# msr501.net
KiCad netlist of a schematic drawn in Altium Designer
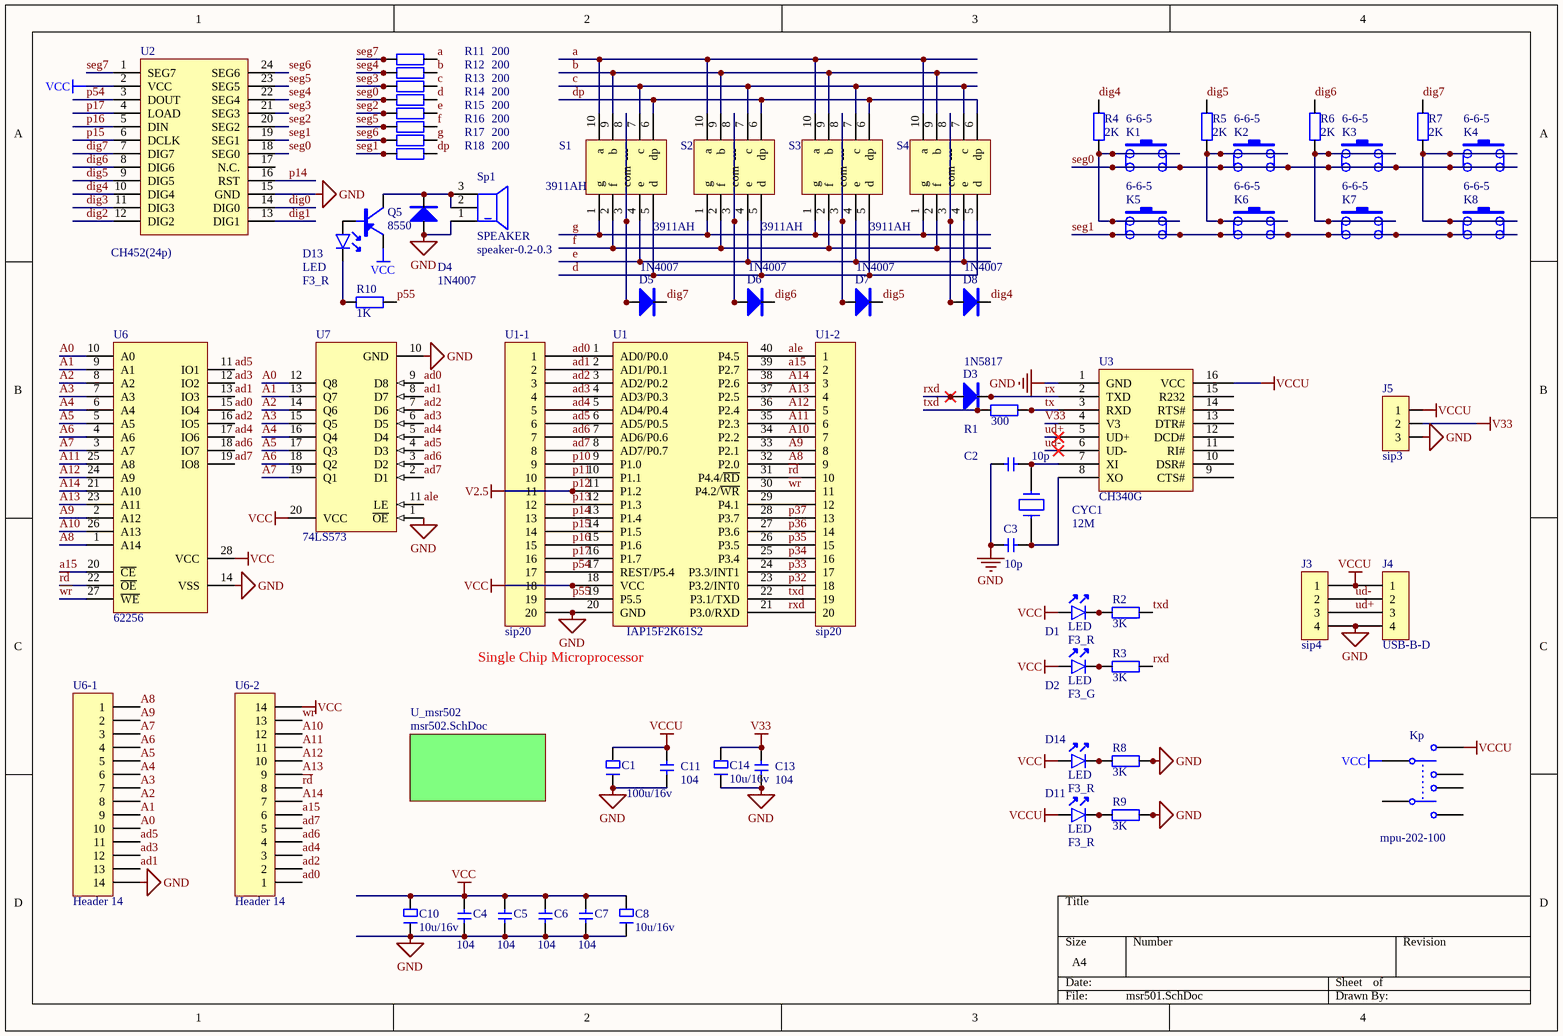
[diagram p0: msr501.SchDoc]

(export (version "E")
  (design (tool "Eeschema 10.0.6"))
  (components
    (comp (ref "C1")
      (value "100u/16v")
      (footprint "rb.1/.2")
      (description "Electrolytic Capacitor")
      (libsource (lib "msr3") (part "ELECTRO1"))
    )
    (comp (ref "C2")
      (value "10p")
      (footprint "CAP010805")
      (fields (field (name "Comment") "CAP"))
      (libsource (lib "lab_iap") (part "CAP"))
    )
    (comp (ref "C3")
      (value "10p")
      (footprint "CAP010805")
      (fields (field (name "Comment") "CAP"))
      (libsource (lib "lab_iap") (part "CAP"))
    )
    (comp (ref "C4")
      (value "104")
      (footprint "CAP010805")
      (description "Capacitor")
      (libsource (lib "*") (part "CAP"))
    )
    (comp (ref "C5")
      (value "104")
      (footprint "CAP010805")
      (description "Capacitor")
      (libsource (lib "*") (part "CAP"))
    )
    (comp (ref "C6")
      (value "104")
      (footprint "CAP010805")
      (description "Capacitor")
      (libsource (lib "m2t1") (part "CAP"))
    )
    (comp (ref "C7")
      (value "104")
      (footprint "CAP010805")
      (description "Capacitor")
      (libsource (lib "*") (part "CAP"))
    )
    (comp (ref "C8")
      (value "10u/16v")
      (footprint "rb.1/.2")
      (description "Electrolytic Capacitor")
      (fields (field (name "Comment") "100u/16v"))
      (libsource (lib "msr3") (part "ELECTRO1"))
    )
    (comp (ref "C10")
      (value "10u/16v")
      (footprint "rb.1/.2")
      (description "Electrolytic Capacitor")
      (fields (field (name "Comment") "100u/16v"))
      (libsource (lib "msr3") (part "ELECTRO1"))
    )
    (comp (ref "C11")
      (value "104")
      (footprint "CAP010805")
      (description "Capacitor")
      (libsource (lib "*") (part "CAP"))
    )
    (comp (ref "C13")
      (value "104")
      (footprint "CAP010805")
      (description "Capacitor")
      (fields (field (name "ALTIUM_VALUE") "104"))
      (libsource (lib "*") (part "CAP"))
    )
    (comp (ref "C14")
      (value "10u/16v")
      (footprint "rb.1/.2")
      (description "Electrolytic Capacitor")
      (libsource (lib "msr3") (part "ELECTRO1"))
    )
    (comp (ref "CYC1")
      (value "12M")
      (footprint "cyc-rad")
      (description "Crystal")
      (fields (field (name "Comment") "12Mhz"))
      (libsource (lib "*") (part "CRYSTAL"))
    )
    (comp (ref "D1")
      (value "LED")
      (footprint "led-3")
      (fields (field (name "ALTIUM_VALUE") "F3_R"))
      (libsource (lib "PCB_prj3") (part "LED"))
    )
    (comp (ref "D2")
      (value "LED")
      (footprint "led-3")
      (fields (field (name "ALTIUM_VALUE") "F3_G"))
      (libsource (lib "PCB_prj3") (part "LED"))
    )
    (comp (ref "D3")
      (value "1N5817")
      (footprint "smc03")
      (fields (field (name "Comment") "sma03"))
      (libsource (lib "mpll3") (part "sma03"))
    )
    (comp (ref "D4")
      (value "1N4007")
      (footprint "smc03")
      (fields (field (name "Comment") "sma03"))
      (libsource (lib "mpll3") (part "sma03"))
    )
    (comp (ref "D5")
      (value "1N4007")
      (footprint "smc03")
      (fields (field (name "Comment") "sma03"))
      (libsource (lib "mpll3") (part "sma03"))
    )
    (comp (ref "D6")
      (value "1N4007")
      (footprint "smc03")
      (fields (field (name "Comment") "sma03"))
      (libsource (lib "mpll3") (part "sma03"))
    )
    (comp (ref "D7")
      (value "1N4007")
      (footprint "smc03")
      (fields (field (name "Comment") "sma03"))
      (libsource (lib "mpll3") (part "sma03"))
    )
    (comp (ref "D8")
      (value "1N4007")
      (footprint "smc03")
      (fields (field (name "Comment") "sma03"))
      (libsource (lib "mpll3") (part "sma03"))
    )
    (comp (ref "D11")
      (value "LED")
      (footprint "led-3")
      (fields (field (name "ALTIUM_VALUE") "F3_R"))
      (libsource (lib "PCB_prj3") (part "LED"))
    )
    (comp (ref "D13")
      (value "LED")
      (footprint "led-3")
      (fields (field (name "ALTIUM_VALUE") "F3_R"))
      (libsource (lib "") (part "LED_1"))
    )
    (comp (ref "D14")
      (value "LED")
      (footprint "led-3")
      (fields (field (name "ALTIUM_VALUE") "F3_R"))
      (libsource (lib "PCB_prj3") (part "LED"))
    )
    (comp (ref "J3")
      (value "sip4")
      (footprint "SIP4")
      (description "Connector")
      (fields (field (name "Comment") "USB-a"))
      (libsource (lib "") (part "CON4_1"))
    )
    (comp (ref "J4")
      (value "USB-B-D")
      (footprint "USB_b")
      (description "Connector")
      (libsource (lib "MyInt_Lib") (part "CON4"))
    )
    (comp (ref "J5")
      (value "sip3")
      (footprint "SIP3")
      (description "Connector")
      (fields (field (name "Comment") "CON3"))
      (libsource (lib "mtr1_1") (part "CON3"))
    )
    (comp (ref "K1") (value "6-6-5") (footprint "pb6_6") (libsource (lib "*") (part "SW-PB2")))
    (comp (ref "K2") (value "6-6-5") (footprint "pb6_6") (libsource (lib "*") (part "SW-PB2")))
    (comp (ref "K3") (value "6-6-5") (footprint "pb6_6") (libsource (lib "*") (part "SW-PB2")))
    (comp (ref "K4") (value "6-6-5") (footprint "pb6_6") (libsource (lib "*") (part "SW-PB2")))
    (comp (ref "K5") (value "6-6-5") (footprint "pb6_6") (libsource (lib "*") (part "SW-PB2")))
    (comp (ref "K6") (value "6-6-5") (footprint "pb6_6") (libsource (lib "*") (part "SW-PB2")))
    (comp (ref "K7") (value "6-6-5") (footprint "pb6_6") (libsource (lib "*") (part "SW-PB2")))
    (comp (ref "K8") (value "6-6-5") (footprint "pb6_6") (libsource (lib "*") (part "SW-PB2")))
    (comp (ref "Kp")
      (value "mpu-202-100")
      (footprint "DPDT-6")
      (description "Double-Pole, Double-Throw Switch")
      (fields (field (name "Comment") "SW-DPDT") (field (name "PUBLISHER") "Altium Limited"))
      (libsource (lib "m2t3") (part "SW-DPDT"))
    )
    (comp (ref "Q5") (value "8550") (footprint "to-92a") (libsource (lib "PCB_prj3") (part "PNP")))
    (comp (ref "R1")
      (value "300")
      (footprint "a038050")
      (description "Resistor")
      (fields (field (name "Comment") "Res2") (field (name "PUBLISHER") "Altium Limited"))
      (libsource (lib "msr4") (part "Res22"))
    )
    (comp (ref "R2")
      (value "3K")
      (footprint "a038050")
      (description "Resistor")
      (fields (field (name "Comment") "Res2") (field (name "PUBLISHER") "Altium Limited"))
      (libsource (lib "msr4") (part "Res22"))
    )
    (comp (ref "R3")
      (value "3K")
      (footprint "a038050")
      (description "Resistor")
      (fields (field (name "Comment") "Res2") (field (name "PUBLISHER") "Altium Limited"))
      (libsource (lib "msr4") (part "Res22"))
    )
    (comp (ref "R4")
      (value "2K")
      (footprint "a038050")
      (description "Resistor")
      (fields (field (name "Comment") "Res2") (field (name "PUBLISHER") "Altium Limited"))
      (libsource (lib "") (part "Res22_1"))
    )
    (comp (ref "R5")
      (value "2K")
      (footprint "a038050")
      (description "Resistor")
      (fields (field (name "Comment") "Res2") (field (name "PUBLISHER") "Altium Limited"))
      (libsource (lib "") (part "Res22_1"))
    )
    (comp (ref "R6")
      (value "2K")
      (footprint "a038050")
      (description "Resistor")
      (fields (field (name "Comment") "Res2") (field (name "PUBLISHER") "Altium Limited"))
      (libsource (lib "") (part "Res22_1"))
    )
    (comp (ref "R7")
      (value "2K")
      (footprint "a038050")
      (description "Resistor")
      (fields (field (name "Comment") "Res2") (field (name "PUBLISHER") "Altium Limited"))
      (libsource (lib "") (part "Res22_1"))
    )
    (comp (ref "R8")
      (value "3K")
      (footprint "a038050")
      (description "Resistor")
      (fields (field (name "Comment") "Res2") (field (name "PUBLISHER") "Altium Limited"))
      (libsource (lib "msr4") (part "Res22"))
    )
    (comp (ref "R9")
      (value "3K")
      (footprint "a038050")
      (description "Resistor")
      (fields (field (name "Comment") "Res2") (field (name "PUBLISHER") "Altium Limited"))
      (libsource (lib "msr4") (part "Res22"))
    )
    (comp (ref "R10")
      (value "1K")
      (footprint "a038050")
      (description "Resistor")
      (fields (field (name "Comment") "Res2") (field (name "PUBLISHER") "Altium Limited"))
      (libsource (lib "msr4") (part "Res22"))
    )
    (comp (ref "R11")
      (value "200")
      (footprint "a038050")
      (description "Resistor")
      (fields (field (name "Comment") "Res2") (field (name "PUBLISHER") "Altium Limited"))
      (libsource (lib "msr4") (part "Res22"))
    )
    (comp (ref "R12")
      (value "200")
      (footprint "a038050")
      (description "Resistor")
      (fields (field (name "Comment") "Res2") (field (name "PUBLISHER") "Altium Limited"))
      (libsource (lib "msr4") (part "Res22"))
    )
    (comp (ref "R13")
      (value "200")
      (footprint "a038050")
      (description "Resistor")
      (fields (field (name "Comment") "Res2") (field (name "PUBLISHER") "Altium Limited"))
      (libsource (lib "msr4") (part "Res22"))
    )
    (comp (ref "R14")
      (value "200")
      (footprint "a038050")
      (description "Resistor")
      (fields (field (name "Comment") "Res2") (field (name "PUBLISHER") "Altium Limited"))
      (libsource (lib "msr4") (part "Res22"))
    )
    (comp (ref "R15")
      (value "200")
      (footprint "a038050")
      (description "Resistor")
      (fields (field (name "Comment") "Res2") (field (name "PUBLISHER") "Altium Limited"))
      (libsource (lib "msr4") (part "Res22"))
    )
    (comp (ref "R16")
      (value "200")
      (footprint "a038050")
      (description "Resistor")
      (fields (field (name "Comment") "Res2") (field (name "PUBLISHER") "Altium Limited"))
      (libsource (lib "msr4") (part "Res22"))
    )
    (comp (ref "R17")
      (value "200")
      (footprint "a038050")
      (description "Resistor")
      (fields (field (name "Comment") "Res2") (field (name "PUBLISHER") "Altium Limited"))
      (libsource (lib "msr4") (part "Res22"))
    )
    (comp (ref "R18")
      (value "200")
      (footprint "a038050")
      (description "Resistor")
      (fields (field (name "Comment") "Res2") (field (name "PUBLISHER") "Altium Limited"))
      (libsource (lib "msr4") (part "Res22"))
    )
    (comp (ref "S1") (value "3911AH") (footprint "LED10s") (libsource (lib "m2t1") (part "DS1")))
    (comp (ref "S2") (value "3911AH") (footprint "LED10s") (libsource (lib "m2t1") (part "DS1")))
    (comp (ref "S3") (value "3911AH") (footprint "LED10s") (libsource (lib "m2t1") (part "DS1")))
    (comp (ref "S4") (value "3911AH") (footprint "LED10s") (libsource (lib "m2t1") (part "DS1")))
    (comp (ref "Sp1")
      (value "SPEAKER")
      (footprint "sp0.23")
      (description "SPEAKER sip0.2/0.3")
      (fields (field (name "ALTIUM_VALUE") "speaker-0.2-0.3"))
      (libsource (lib "m2t5") (part "SPEAKER"))
    )
    (comp (ref "U1")
      (value "IAP15F2K61S2")
      (footprint "DIP40")
      (fields (field (name "Comment") "单片机IAP15F2K61S2"))
      (libsource (lib "NEW") (part "Component_3"))
    )
    (comp (ref "U1-1")
      (value "sip20")
      (footprint "msr2:HDR1X20")
      (description "Header, 20-Pin")
      (fields (field (name "Comment") "Header 20") (field (name "PUBLISHER") "Altium Limited"))
      (libsource (lib "Miscellaneous Connectors") (part "Header 20"))
    )
    (comp (ref "U1-2")
      (value "sip20")
      (footprint "HDR1X20")
      (description "Header, 20-Pin")
      (fields (field (name "Comment") "Header 20") (field (name "PUBLISHER") "Altium Limited"))
      (libsource (lib "") (part "Header 20_1"))
    )
    (comp (ref "U2")
      (value "CH452(24p)")
      (footprint "dip24")
      (fields (field (name "Comment") "CH451"))
      (libsource (lib "*") (part "CH451"))
    )
    (comp (ref "U3") (value "CH340G") (footprint "SOP-16") (libsource (lib "msr") (part "CH340G")))
    (comp (ref "U6") (value "62256") (footprint "62256") (libsource (lib "MyLib") (part "62256")))
    (comp (ref "U6-1")
      (value "Header 14")
      (footprint "HDR1X14C")
      (description "Header, 14-Pin")
      (fields (field (name "PUBLISHER") "Altium Limited"))
      (libsource (lib "Miscellaneous Connectors") (part "Header 14"))
    )
    (comp (ref "U6-2")
      (value "Header 14")
      (footprint "HDR1X14C")
      (description "Header, 14-Pin")
      (fields (field (name "PUBLISHER") "Altium Limited"))
      (libsource (lib "") (part "Header 14_1"))
    )
    (comp (ref "U7")
      (value "74LS573")
      (footprint "DIP20")
      (description "Octal D Latch with 3-State Output")
      (fields (field (name "Comment") "DM74LS573N") (field (name "PUBLISHER") "Altium Limited"))
      (libsource (lib "FSC Logic Latch") (part "DM74LS573N"))
    )
  )
  (nets
    (net (code "2") (name "/A0") (class "Default")
      (node (ref "U6") (pin "10") (pinfunction "A0_10") (pintype "passive"))
      (node (ref "U6-1") (pin "10") (pinfunction "10_10") (pintype "passive"))
      (node (ref "U7") (pin "12") (pinfunction "Q8_12") (pintype "tri_state"))
    )
    (net (code "3") (name "/A1") (class "Default")
      (node (ref "U6") (pin "9") (pinfunction "A1_9") (pintype "passive"))
      (node (ref "U6-1") (pin "9") (pinfunction "9_9") (pintype "passive"))
      (node (ref "U7") (pin "13") (pinfunction "Q7_13") (pintype "tri_state"))
    )
    (net (code "4") (name "/A2") (class "Default")
      (node (ref "U6") (pin "8") (pinfunction "A2_8") (pintype "passive"))
      (node (ref "U6-1") (pin "8") (pinfunction "8_8") (pintype "passive"))
      (node (ref "U7") (pin "14") (pinfunction "Q6_14") (pintype "tri_state"))
    )
    (net (code "5") (name "/A3") (class "Default")
      (node (ref "U6") (pin "7") (pinfunction "A3_7") (pintype "passive"))
      (node (ref "U6-1") (pin "7") (pinfunction "7_7") (pintype "passive"))
      (node (ref "U7") (pin "15") (pinfunction "Q5_15") (pintype "tri_state"))
    )
    (net (code "6") (name "/A4") (class "Default")
      (node (ref "U6") (pin "6") (pinfunction "A4_6") (pintype "passive"))
      (node (ref "U6-1") (pin "6") (pinfunction "6_6") (pintype "passive"))
      (node (ref "U7") (pin "16") (pinfunction "Q4_16") (pintype "tri_state"))
    )
    (net (code "7") (name "/A5") (class "Default")
      (node (ref "U6") (pin "5") (pinfunction "A5_5") (pintype "passive"))
      (node (ref "U6-1") (pin "5") (pinfunction "5_5") (pintype "passive"))
      (node (ref "U7") (pin "17") (pinfunction "Q3_17") (pintype "tri_state"))
    )
    (net (code "8") (name "/A6") (class "Default")
      (node (ref "U6") (pin "4") (pinfunction "A6_4") (pintype "passive"))
      (node (ref "U6-1") (pin "4") (pinfunction "4_4") (pintype "passive"))
      (node (ref "U7") (pin "18") (pinfunction "Q2_18") (pintype "tri_state"))
    )
    (net (code "9") (name "/A7") (class "Default")
      (node (ref "U6") (pin "3") (pinfunction "A7_3") (pintype "passive"))
      (node (ref "U6-1") (pin "3") (pinfunction "3_3") (pintype "passive"))
      (node (ref "U7") (pin "19") (pinfunction "Q1_19") (pintype "tri_state"))
    )
    (net (code "10") (name "/A8") (class "Default")
      (node (ref "U1") (pin "32") (pinfunction "P2.0_32") (pintype "passive"))
      (node (ref "U1-2") (pin "9") (pinfunction "9_9") (pintype "passive"))
      (node (ref "U6") (pin "1") (pinfunction "A14_1") (pintype "passive"))
      (node (ref "U6-1") (pin "1") (pinfunction "1_1") (pintype "passive"))
    )
    (net (code "11") (name "/A9") (class "Default")
      (node (ref "U1") (pin "33") (pinfunction "P2.1_33") (pintype "passive"))
      (node (ref "U1-2") (pin "8") (pinfunction "8_8") (pintype "passive"))
      (node (ref "U6") (pin "2") (pinfunction "A12_2") (pintype "passive"))
      (node (ref "U6-1") (pin "2") (pinfunction "2_2") (pintype "passive"))
    )
    (net (code "12") (name "/A10") (class "Default")
      (node (ref "U1") (pin "34") (pinfunction "P2.2_34") (pintype "passive"))
      (node (ref "U1-2") (pin "7") (pinfunction "7_7") (pintype "passive"))
      (node (ref "U6") (pin "26") (pinfunction "A13_26") (pintype "passive"))
      (node (ref "U6-2") (pin "12") (pinfunction "12_12") (pintype "passive"))
    )
    (net (code "13") (name "/A11") (class "Default")
      (node (ref "U1") (pin "35") (pinfunction "P2.3_35") (pintype "passive"))
      (node (ref "U1-2") (pin "6") (pinfunction "6_6") (pintype "passive"))
      (node (ref "U6") (pin "25") (pinfunction "A8_25") (pintype "passive"))
      (node (ref "U6-2") (pin "11") (pinfunction "11_11") (pintype "passive"))
    )
    (net (code "14") (name "/A12") (class "Default")
      (node (ref "U1") (pin "36") (pinfunction "P2.4_36") (pintype "passive"))
      (node (ref "U1-2") (pin "5") (pinfunction "5_5") (pintype "passive"))
      (node (ref "U6") (pin "24") (pinfunction "A9_24") (pintype "passive"))
      (node (ref "U6-2") (pin "10") (pinfunction "10_10") (pintype "passive"))
    )
    (net (code "15") (name "/A13") (class "Default")
      (node (ref "U1") (pin "37") (pinfunction "P2.5_37") (pintype "passive"))
      (node (ref "U1-2") (pin "4") (pinfunction "4_4") (pintype "passive"))
      (node (ref "U6") (pin "23") (pinfunction "A11_23") (pintype "passive"))
      (node (ref "U6-2") (pin "9") (pinfunction "9_9") (pintype "passive"))
    )
    (net (code "16") (name "/A14") (class "Default")
      (node (ref "U1") (pin "38") (pinfunction "P2.6_38") (pintype "passive"))
      (node (ref "U1-2") (pin "3") (pinfunction "3_3") (pintype "passive"))
      (node (ref "U6") (pin "21") (pinfunction "A10_21") (pintype "passive"))
      (node (ref "U6-2") (pin "7") (pinfunction "7_7") (pintype "passive"))
    )
    (net (code "17") (name "/a") (class "Default")
      (node (ref "R11") (pin "1") (pinfunction "1_1") (pintype "passive"))
      (node (ref "R11") (pin "3") (pinfunction "3_3") (pintype "passive"))
      (node (ref "S1") (pin "10") (pinfunction "a_10") (pintype "passive"))
      (node (ref "S2") (pin "10") (pinfunction "a_10") (pintype "passive"))
      (node (ref "S3") (pin "10") (pinfunction "a_10") (pintype "passive"))
      (node (ref "S4") (pin "10") (pinfunction "a_10") (pintype "passive"))
    )
    (net (code "18") (name "/a15") (class "Default")
      (node (ref "U1") (pin "39") (pinfunction "P2.7_39") (pintype "passive"))
      (node (ref "U1-2") (pin "2") (pinfunction "2_2") (pintype "passive"))
      (node (ref "U6") (pin "20") (pinfunction "~{CE}_20") (pintype "passive"))
      (node (ref "U6-2") (pin "6") (pinfunction "6_6") (pintype "passive"))
    )
    (net (code "19") (name "/ad0") (class "Default")
      (node (ref "U1") (pin "1") (pinfunction "AD0/P0.0_1") (pintype "passive"))
      (node (ref "U1-1") (pin "1") (pinfunction "1_1") (pintype "passive"))
      (node (ref "U6") (pin "15") (pinfunction "IO4_15") (pintype "passive"))
      (node (ref "U6-2") (pin "1") (pinfunction "1_1") (pintype "passive"))
      (node (ref "U7") (pin "9") (pinfunction "D8_9") (pintype "input"))
    )
    (net (code "20") (name "/ad1") (class "Default")
      (node (ref "U1") (pin "2") (pinfunction "AD1/P0.1_2") (pintype "passive"))
      (node (ref "U1-1") (pin "2") (pinfunction "2_2") (pintype "passive"))
      (node (ref "U6") (pin "13") (pinfunction "IO3_13") (pintype "passive"))
      (node (ref "U6-1") (pin "13") (pinfunction "13_13") (pintype "passive"))
      (node (ref "U7") (pin "8") (pinfunction "D7_8") (pintype "input"))
    )
    (net (code "21") (name "/ad2") (class "Default")
      (node (ref "U1") (pin "3") (pinfunction "AD2/P0.2_3") (pintype "passive"))
      (node (ref "U1-1") (pin "3") (pinfunction "3_3") (pintype "passive"))
      (node (ref "U6") (pin "16") (pinfunction "IO5_16") (pintype "passive"))
      (node (ref "U6-2") (pin "2") (pinfunction "2_2") (pintype "passive"))
      (node (ref "U7") (pin "7") (pinfunction "D6_7") (pintype "input"))
    )
    (net (code "22") (name "/ad3") (class "Default")
      (node (ref "U1") (pin "4") (pinfunction "AD3/P0.3_4") (pintype "passive"))
      (node (ref "U1-1") (pin "4") (pinfunction "4_4") (pintype "passive"))
      (node (ref "U6") (pin "12") (pinfunction "IO2_12") (pintype "passive"))
      (node (ref "U6-1") (pin "12") (pinfunction "12_12") (pintype "passive"))
      (node (ref "U7") (pin "6") (pinfunction "D5_6") (pintype "input"))
    )
    (net (code "23") (name "/ad4") (class "Default")
      (node (ref "U1") (pin "5") (pinfunction "AD4/P0.4_5") (pintype "passive"))
      (node (ref "U1-1") (pin "5") (pinfunction "5_5") (pintype "passive"))
      (node (ref "U6") (pin "17") (pinfunction "IO6_17") (pintype "passive"))
      (node (ref "U6-2") (pin "3") (pinfunction "3_3") (pintype "passive"))
      (node (ref "U7") (pin "5") (pinfunction "D4_5") (pintype "input"))
    )
    (net (code "24") (name "/ad5") (class "Default")
      (node (ref "U1") (pin "6") (pinfunction "AD5/P0.5_6") (pintype "passive"))
      (node (ref "U1-1") (pin "6") (pinfunction "6_6") (pintype "passive"))
      (node (ref "U6") (pin "11") (pinfunction "IO1_11") (pintype "passive"))
      (node (ref "U6-1") (pin "11") (pinfunction "11_11") (pintype "passive"))
      (node (ref "U7") (pin "4") (pinfunction "D3_4") (pintype "input"))
    )
    (net (code "25") (name "/ad6") (class "Default")
      (node (ref "U1") (pin "7") (pinfunction "AD6/P0.6_7") (pintype "passive"))
      (node (ref "U1-1") (pin "7") (pinfunction "7_7") (pintype "passive"))
      (node (ref "U6") (pin "18") (pinfunction "IO7_18") (pintype "passive"))
      (node (ref "U6-2") (pin "4") (pinfunction "4_4") (pintype "passive"))
      (node (ref "U7") (pin "3") (pinfunction "D2_3") (pintype "input"))
    )
    (net (code "26") (name "/ad7") (class "Default")
      (node (ref "U1") (pin "8") (pinfunction "AD7/P0.7_8") (pintype "passive"))
      (node (ref "U1-1") (pin "8") (pinfunction "8_8") (pintype "passive"))
      (node (ref "U6") (pin "19") (pinfunction "IO8_19") (pintype "passive"))
      (node (ref "U6-2") (pin "5") (pinfunction "5_5") (pintype "passive"))
      (node (ref "U7") (pin "2") (pinfunction "D1_2") (pintype "input"))
    )
    (net (code "27") (name "/ale") (class "Default")
      (node (ref "U1") (pin "40") (pinfunction "P4.5_40") (pintype "passive"))
      (node (ref "U1-2") (pin "1") (pinfunction "1_1") (pintype "passive"))
      (node (ref "U7") (pin "11") (pinfunction "LE_11") (pintype "input"))
    )
    (net (code "28") (name "/b") (class "Default")
      (node (ref "R12") (pin "1") (pinfunction "1_1") (pintype "passive"))
      (node (ref "R12") (pin "3") (pinfunction "3_3") (pintype "passive"))
      (node (ref "S1") (pin "9") (pinfunction "b_9") (pintype "passive"))
      (node (ref "S2") (pin "9") (pinfunction "b_9") (pintype "passive"))
      (node (ref "S3") (pin "9") (pinfunction "b_9") (pintype "passive"))
      (node (ref "S4") (pin "9") (pinfunction "b_9") (pintype "passive"))
    )
    (net (code "29") (name "/c") (class "Default")
      (node (ref "R13") (pin "1") (pinfunction "1_1") (pintype "passive"))
      (node (ref "R13") (pin "3") (pinfunction "3_3") (pintype "passive"))
      (node (ref "S1") (pin "7") (pinfunction "c_7") (pintype "passive"))
      (node (ref "S2") (pin "7") (pinfunction "c_7") (pintype "passive"))
      (node (ref "S3") (pin "7") (pinfunction "c_7") (pintype "passive"))
      (node (ref "S4") (pin "7") (pinfunction "c_7") (pintype "passive"))
    )
    (net (code "30") (name "/d") (class "Default")
      (node (ref "R14") (pin "1") (pinfunction "1_1") (pintype "passive"))
      (node (ref "R14") (pin "3") (pinfunction "3_3") (pintype "passive"))
      (node (ref "S1") (pin "5") (pinfunction "d_5") (pintype "passive"))
      (node (ref "S2") (pin "5") (pinfunction "d_5") (pintype "passive"))
      (node (ref "S3") (pin "5") (pinfunction "d_5") (pintype "passive"))
      (node (ref "S4") (pin "5") (pinfunction "d_5") (pintype "passive"))
    )
    (net (code "31") (name "/dig0") (class "Default")
      (node (ref "U2") (pin "14") (pinfunction "DIG0_14") (pintype "passive"))
    )
    (net (code "32") (name "/dig1") (class "Default")
      (node (ref "U2") (pin "13") (pinfunction "DIG1_13") (pintype "passive"))
    )
    (net (code "33") (name "/dig2") (class "Default")
      (node (ref "U2") (pin "12") (pinfunction "DIG2_12") (pintype "passive"))
    )
    (net (code "34") (name "/dig3") (class "Default")
      (node (ref "U2") (pin "11") (pinfunction "DIG3_11") (pintype "passive"))
    )
    (net (code "35") (name "/dig4") (class "Default")
      (node (ref "D8") (pin "1") (pinfunction "1_1") (pintype "passive"))
      (node (ref "D8") (pin "3") (pinfunction "3_3") (pintype "passive"))
      (node (ref "R4") (pin "2") (pinfunction "2_2") (pintype "passive"))
      (node (ref "R4") (pin "4") (pinfunction "4_4") (pintype "passive"))
      (node (ref "U2") (pin "10") (pinfunction "DIG4_10") (pintype "passive"))
    )
    (net (code "36") (name "/dig5") (class "Default")
      (node (ref "D7") (pin "1") (pinfunction "1_1") (pintype "passive"))
      (node (ref "D7") (pin "3") (pinfunction "3_3") (pintype "passive"))
      (node (ref "R5") (pin "2") (pinfunction "2_2") (pintype "passive"))
      (node (ref "R5") (pin "4") (pinfunction "4_4") (pintype "passive"))
      (node (ref "U2") (pin "9") (pinfunction "DIG5_9") (pintype "passive"))
    )
    (net (code "37") (name "/dig6") (class "Default")
      (node (ref "D6") (pin "1") (pinfunction "1_1") (pintype "passive"))
      (node (ref "D6") (pin "3") (pinfunction "3_3") (pintype "passive"))
      (node (ref "R6") (pin "2") (pinfunction "2_2") (pintype "passive"))
      (node (ref "R6") (pin "4") (pinfunction "4_4") (pintype "passive"))
      (node (ref "U2") (pin "8") (pinfunction "DIG6_8") (pintype "passive"))
    )
    (net (code "38") (name "/dig7") (class "Default")
      (node (ref "D5") (pin "1") (pinfunction "1_1") (pintype "passive"))
      (node (ref "D5") (pin "3") (pinfunction "3_3") (pintype "passive"))
      (node (ref "R7") (pin "2") (pinfunction "2_2") (pintype "passive"))
      (node (ref "R7") (pin "4") (pinfunction "4_4") (pintype "passive"))
      (node (ref "U2") (pin "7") (pinfunction "DIG7_7") (pintype "passive"))
    )
    (net (code "39") (name "/dp") (class "Default")
      (node (ref "R18") (pin "1") (pinfunction "1_1") (pintype "passive"))
      (node (ref "R18") (pin "3") (pinfunction "3_3") (pintype "passive"))
      (node (ref "S1") (pin "6") (pinfunction "dp_6") (pintype "passive"))
      (node (ref "S2") (pin "6") (pinfunction "dp_6") (pintype "passive"))
      (node (ref "S3") (pin "6") (pinfunction "dp_6") (pintype "passive"))
      (node (ref "S4") (pin "6") (pinfunction "dp_6") (pintype "passive"))
    )
    (net (code "40") (name "/e") (class "Default")
      (node (ref "R15") (pin "1") (pinfunction "1_1") (pintype "passive"))
      (node (ref "R15") (pin "3") (pinfunction "3_3") (pintype "passive"))
      (node (ref "S1") (pin "4") (pinfunction "e_4") (pintype "passive"))
      (node (ref "S2") (pin "4") (pinfunction "e_4") (pintype "passive"))
      (node (ref "S3") (pin "4") (pinfunction "e_4") (pintype "passive"))
      (node (ref "S4") (pin "4") (pinfunction "e_4") (pintype "passive"))
    )
    (net (code "41") (name "/f") (class "Default")
      (node (ref "R16") (pin "1") (pinfunction "1_1") (pintype "passive"))
      (node (ref "R16") (pin "3") (pinfunction "3_3") (pintype "passive"))
      (node (ref "S1") (pin "2") (pinfunction "f_2") (pintype "passive"))
      (node (ref "S2") (pin "2") (pinfunction "f_2") (pintype "passive"))
      (node (ref "S3") (pin "2") (pinfunction "f_2") (pintype "passive"))
      (node (ref "S4") (pin "2") (pinfunction "f_2") (pintype "passive"))
    )
    (net (code "42") (name "/g") (class "Default")
      (node (ref "R17") (pin "1") (pinfunction "1_1") (pintype "passive"))
      (node (ref "R17") (pin "3") (pinfunction "3_3") (pintype "passive"))
      (node (ref "S1") (pin "1") (pinfunction "g_1") (pintype "passive"))
      (node (ref "S2") (pin "1") (pinfunction "g_1") (pintype "passive"))
      (node (ref "S3") (pin "1") (pinfunction "g_1") (pintype "passive"))
      (node (ref "S4") (pin "1") (pinfunction "g_1") (pintype "passive"))
    )
    (net (code "43") (name "/p10") (class "Default")
      (node (ref "U1") (pin "9") (pinfunction "P1.0_9") (pintype "passive"))
      (node (ref "U1-1") (pin "9") (pinfunction "9_9") (pintype "passive"))
    )
    (net (code "44") (name "/p11") (class "Default")
      (node (ref "U1") (pin "10") (pinfunction "P1.1_10") (pintype "passive"))
      (node (ref "U1-1") (pin "10") (pinfunction "10_10") (pintype "passive"))
    )
    (net (code "45") (name "/p13") (class "Default")
      (node (ref "U1") (pin "12") (pinfunction "P1.3_12") (pintype "passive"))
      (node (ref "U1-1") (pin "12") (pinfunction "12_12") (pintype "passive"))
    )
    (net (code "46") (name "/p14") (class "Default")
      (node (ref "U1") (pin "13") (pinfunction "P1.4_13") (pintype "passive"))
      (node (ref "U1-1") (pin "13") (pinfunction "13_13") (pintype "passive"))
      (node (ref "U2") (pin "16") (pinfunction "RST_16") (pintype "passive"))
    )
    (net (code "47") (name "/p15") (class "Default")
      (node (ref "U1") (pin "14") (pinfunction "P1.5_14") (pintype "passive"))
      (node (ref "U1-1") (pin "14") (pinfunction "14_14") (pintype "passive"))
      (node (ref "U2") (pin "6") (pinfunction "DCLK_6") (pintype "passive"))
    )
    (net (code "48") (name "/p16") (class "Default")
      (node (ref "U1") (pin "15") (pinfunction "P1.6_15") (pintype "passive"))
      (node (ref "U1-1") (pin "15") (pinfunction "15_15") (pintype "passive"))
      (node (ref "U2") (pin "5") (pinfunction "DIN_5") (pintype "passive"))
    )
    (net (code "49") (name "/p17") (class "Default")
      (node (ref "U1") (pin "16") (pinfunction "P1.7_16") (pintype "passive"))
      (node (ref "U1-1") (pin "16") (pinfunction "16_16") (pintype "passive"))
      (node (ref "U2") (pin "4") (pinfunction "LOAD_4") (pintype "passive"))
    )
    (net (code "50") (name "/p32") (class "Default")
      (node (ref "U1") (pin "23") (pinfunction "P3.2/INT0_23") (pintype "passive"))
      (node (ref "U1-2") (pin "18") (pinfunction "18_18") (pintype "passive"))
    )
    (net (code "51") (name "/p33") (class "Default")
      (node (ref "U1") (pin "24") (pinfunction "P3.3/INT1_24") (pintype "passive"))
      (node (ref "U1-2") (pin "17") (pinfunction "17_17") (pintype "passive"))
    )
    (net (code "52") (name "/p34") (class "Default")
      (node (ref "U1") (pin "25") (pinfunction "P3.4_25") (pintype "passive"))
      (node (ref "U1-2") (pin "16") (pinfunction "16_16") (pintype "passive"))
    )
    (net (code "53") (name "/p35") (class "Default")
      (node (ref "U1") (pin "26") (pinfunction "P3.5_26") (pintype "passive"))
      (node (ref "U1-2") (pin "15") (pinfunction "15_15") (pintype "passive"))
    )
    (net (code "54") (name "/p36") (class "Default")
      (node (ref "U1") (pin "27") (pinfunction "P3.6_27") (pintype "passive"))
      (node (ref "U1-2") (pin "14") (pinfunction "14_14") (pintype "passive"))
    )
    (net (code "55") (name "/p37") (class "Default")
      (node (ref "U1") (pin "28") (pinfunction "P3.7_28") (pintype "passive"))
      (node (ref "U1-2") (pin "13") (pinfunction "13_13") (pintype "passive"))
    )
    (net (code "56") (name "/p54") (class "Default")
      (node (ref "U1") (pin "17") (pinfunction "REST/P5.4_17") (pintype "passive"))
      (node (ref "U1-1") (pin "17") (pinfunction "17_17") (pintype "passive"))
      (node (ref "U2") (pin "3") (pinfunction "DOUT_3") (pintype "passive"))
    )
    (net (code "57") (name "/p55") (class "Default")
      (node (ref "R10") (pin "1") (pinfunction "1_1") (pintype "passive"))
      (node (ref "R10") (pin "3") (pinfunction "3_3") (pintype "passive"))
      (node (ref "U1") (pin "19") (pinfunction "P5.5_19") (pintype "passive"))
      (node (ref "U1-1") (pin "19") (pinfunction "19_19") (pintype "passive"))
    )
    (net (code "58") (name "/rx") (class "Default")
      (node (ref "D3") (pin "1") (pinfunction "1_1") (pintype "passive"))
      (node (ref "D3") (pin "3") (pinfunction "3_3") (pintype "passive"))
      (node (ref "U3") (pin "2") (pinfunction "TXD_2") (pintype "passive"))
    )
    (net (code "59") (name "/rxd") (class "Default")
      (node (ref "D3") (pin "2") (pinfunction "2_2") (pintype "passive"))
      (node (ref "D3") (pin "4") (pinfunction "4_4") (pintype "passive"))
      (node (ref "R3") (pin "1") (pinfunction "1_1") (pintype "passive"))
      (node (ref "R3") (pin "3") (pinfunction "3_3") (pintype "passive"))
      (node (ref "U1") (pin "21") (pinfunction "P3.0/RXD_21") (pintype "passive"))
      (node (ref "U1-2") (pin "20") (pinfunction "20_20") (pintype "passive"))
    )
    (net (code "60") (name "/seg0") (class "Default")
      (node (ref "K1") (pin "2") (pinfunction "2_2") (pintype "passive"))
      (node (ref "K1") (pin "3") (pinfunction "3_3") (pintype "passive"))
      (node (ref "K2") (pin "2") (pinfunction "2_2") (pintype "passive"))
      (node (ref "K2") (pin "3") (pinfunction "3_3") (pintype "passive"))
      (node (ref "K3") (pin "2") (pinfunction "2_2") (pintype "passive"))
      (node (ref "K3") (pin "3") (pinfunction "3_3") (pintype "passive"))
      (node (ref "K4") (pin "2") (pinfunction "2_2") (pintype "passive"))
      (node (ref "K4") (pin "3") (pinfunction "3_3") (pintype "passive"))
      (node (ref "R14") (pin "2") (pinfunction "2_2") (pintype "passive"))
      (node (ref "R14") (pin "4") (pinfunction "4_4") (pintype "passive"))
      (node (ref "U2") (pin "18") (pinfunction "SEG0_18") (pintype "passive"))
    )
    (net (code "61") (name "/seg1") (class "Default")
      (node (ref "K5") (pin "2") (pinfunction "2_2") (pintype "passive"))
      (node (ref "K5") (pin "3") (pinfunction "3_3") (pintype "passive"))
      (node (ref "K6") (pin "2") (pinfunction "2_2") (pintype "passive"))
      (node (ref "K6") (pin "3") (pinfunction "3_3") (pintype "passive"))
      (node (ref "K7") (pin "2") (pinfunction "2_2") (pintype "passive"))
      (node (ref "K7") (pin "3") (pinfunction "3_3") (pintype "passive"))
      (node (ref "K8") (pin "2") (pinfunction "2_2") (pintype "passive"))
      (node (ref "K8") (pin "3") (pinfunction "3_3") (pintype "passive"))
      (node (ref "R18") (pin "2") (pinfunction "2_2") (pintype "passive"))
      (node (ref "R18") (pin "4") (pinfunction "4_4") (pintype "passive"))
      (node (ref "U2") (pin "19") (pinfunction "SEG1_19") (pintype "passive"))
    )
    (net (code "62") (name "/seg2") (class "Default")
      (node (ref "R15") (pin "2") (pinfunction "2_2") (pintype "passive"))
      (node (ref "R15") (pin "4") (pinfunction "4_4") (pintype "passive"))
      (node (ref "U2") (pin "20") (pinfunction "SEG2_20") (pintype "passive"))
    )
    (net (code "63") (name "/seg3") (class "Default")
      (node (ref "R13") (pin "2") (pinfunction "2_2") (pintype "passive"))
      (node (ref "R13") (pin "4") (pinfunction "4_4") (pintype "passive"))
      (node (ref "U2") (pin "21") (pinfunction "SEG3_21") (pintype "passive"))
    )
    (net (code "64") (name "/seg4") (class "Default")
      (node (ref "R12") (pin "2") (pinfunction "2_2") (pintype "passive"))
      (node (ref "R12") (pin "4") (pinfunction "4_4") (pintype "passive"))
      (node (ref "U2") (pin "22") (pinfunction "SEG4_22") (pintype "passive"))
    )
    (net (code "65") (name "/seg5") (class "Default")
      (node (ref "R16") (pin "2") (pinfunction "2_2") (pintype "passive"))
      (node (ref "R16") (pin "4") (pinfunction "4_4") (pintype "passive"))
      (node (ref "U2") (pin "23") (pinfunction "SEG5_23") (pintype "passive"))
    )
    (net (code "66") (name "/seg6") (class "Default")
      (node (ref "R17") (pin "2") (pinfunction "2_2") (pintype "passive"))
      (node (ref "R17") (pin "4") (pinfunction "4_4") (pintype "passive"))
      (node (ref "U2") (pin "24") (pinfunction "SEG6_24") (pintype "passive"))
    )
    (net (code "67") (name "/seg7") (class "Default")
      (node (ref "R11") (pin "2") (pinfunction "2_2") (pintype "passive"))
      (node (ref "R11") (pin "4") (pinfunction "4_4") (pintype "passive"))
      (node (ref "U2") (pin "1") (pinfunction "SEG7_1") (pintype "passive"))
    )
    (net (code "68") (name "/tx") (class "Default")
      (node (ref "R1") (pin "1") (pinfunction "1_1") (pintype "passive"))
      (node (ref "R1") (pin "3") (pinfunction "3_3") (pintype "passive"))
      (node (ref "U3") (pin "3") (pinfunction "RXD_3") (pintype "passive"))
    )
    (net (code "69") (name "/txd") (class "Default")
      (node (ref "R1") (pin "2") (pinfunction "2_2") (pintype "passive"))
      (node (ref "R1") (pin "4") (pinfunction "4_4") (pintype "passive"))
      (node (ref "R2") (pin "1") (pinfunction "1_1") (pintype "passive"))
      (node (ref "R2") (pin "3") (pinfunction "3_3") (pintype "passive"))
      (node (ref "U1") (pin "22") (pinfunction "P3.1/TXD_22") (pintype "passive"))
      (node (ref "U1-2") (pin "19") (pinfunction "19_19") (pintype "passive"))
    )
    (net (code "70") (name "/ud+") (class "Default")
      (node (ref "J3") (pin "3") (pinfunction "3_3") (pintype "passive"))
      (node (ref "J4") (pin "3") (pinfunction "3_3") (pintype "passive"))
      (node (ref "U3") (pin "5") (pinfunction "UD+_5") (pintype "passive"))
    )
    (net (code "71") (name "/ud-") (class "Default")
      (node (ref "J3") (pin "2") (pinfunction "2_2") (pintype "passive"))
      (node (ref "J4") (pin "2") (pinfunction "2_2") (pintype "passive"))
      (node (ref "U3") (pin "6") (pinfunction "UD-_6") (pintype "passive"))
    )
    (net (code "72") (name "/~{rd}") (class "Default")
      (node (ref "U1") (pin "31") (pinfunction "P4.4/~{RD}_31") (pintype "passive"))
      (node (ref "U1-2") (pin "10") (pinfunction "10_10") (pintype "passive"))
      (node (ref "U6") (pin "22") (pinfunction "~{OE}_22") (pintype "passive"))
      (node (ref "U6-2") (pin "8") (pinfunction "8_8") (pintype "passive"))
    )
    (net (code "73") (name "/~{wr}") (class "Default")
      (node (ref "U1") (pin "30") (pinfunction "P4.2/~{WR}_30") (pintype "passive"))
      (node (ref "U1-2") (pin "11") (pinfunction "11_11") (pintype "passive"))
      (node (ref "U6") (pin "27") (pinfunction "~{WE}_27") (pintype "passive"))
      (node (ref "U6-2") (pin "13") (pinfunction "13_13") (pintype "passive"))
    )
    (net (code "74") (name "GND") (class "Default")
      (node (ref "C1") (pin "1") (pinfunction "1_1") (pintype "passive"))
      (node (ref "C10") (pin "1") (pinfunction "1_1") (pintype "passive"))
      (node (ref "C11") (pin "2") (pinfunction "2_2") (pintype "passive"))
      (node (ref "C13") (pin "2") (pinfunction "2_2") (pintype "passive"))
      (node (ref "C14") (pin "1") (pinfunction "1_1") (pintype "passive"))
      (node (ref "C2") (pin "2") (pintype "passive"))
      (node (ref "C3") (pin "2") (pintype "passive"))
      (node (ref "C4") (pin "2") (pinfunction "2_2") (pintype "passive"))
      (node (ref "C5") (pin "2") (pinfunction "2_2") (pintype "passive"))
      (node (ref "C6") (pin "2") (pinfunction "2_2") (pintype "passive"))
      (node (ref "C7") (pin "2") (pinfunction "2_2") (pintype "passive"))
      (node (ref "C8") (pin "1") (pinfunction "1_1") (pintype "passive"))
      (node (ref "D4") (pin "2") (pinfunction "2_2") (pintype "passive"))
      (node (ref "D4") (pin "4") (pinfunction "4_4") (pintype "passive"))
      (node (ref "J3") (pin "4") (pinfunction "4_4") (pintype "passive"))
      (node (ref "J4") (pin "4") (pinfunction "4_4") (pintype "passive"))
      (node (ref "J5") (pin "3") (pinfunction "3_3") (pintype "passive"))
      (node (ref "R8") (pin "1") (pinfunction "1_1") (pintype "passive"))
      (node (ref "R8") (pin "3") (pinfunction "3_3") (pintype "passive"))
      (node (ref "R9") (pin "1") (pinfunction "1_1") (pintype "passive"))
      (node (ref "R9") (pin "3") (pinfunction "3_3") (pintype "passive"))
      (node (ref "Sp1") (pin "1") (pinfunction "1_1") (pintype "passive"))
      (node (ref "U1") (pin "20") (pinfunction "GND_20") (pintype "passive"))
      (node (ref "U1-1") (pin "20") (pinfunction "20_20") (pintype "passive"))
      (node (ref "U2") (pin "15") (pinfunction "GND_15") (pintype "passive"))
      (node (ref "U3") (pin "1") (pinfunction "GND_1") (pintype "passive"))
      (node (ref "U6") (pin "14") (pinfunction "VSS_14") (pintype "passive"))
      (node (ref "U6-1") (pin "14") (pinfunction "14_14") (pintype "passive"))
      (node (ref "U7") (pin "1") (pinfunction "~{OE}_1") (pintype "input"))
      (node (ref "U7") (pin "10") (pinfunction "GND_10") (pintype "power_in"))
    )
    (net (code "75") (name "Net-(D1-Pad2)") (class "Default")
      (node (ref "D1") (pin "2") (pinfunction "2_2") (pintype "passive"))
      (node (ref "R2") (pin "2") (pinfunction "2_2") (pintype "passive"))
      (node (ref "R2") (pin "4") (pinfunction "4_4") (pintype "passive"))
    )
    (net (code "76") (name "Net-(D2-Pad2)") (class "Default")
      (node (ref "D2") (pin "2") (pinfunction "2_2") (pintype "passive"))
      (node (ref "R3") (pin "2") (pinfunction "2_2") (pintype "passive"))
      (node (ref "R3") (pin "4") (pinfunction "4_4") (pintype "passive"))
    )
    (net (code "77") (name "Net-(D11-Pad2)") (class "Default")
      (node (ref "D11") (pin "2") (pinfunction "2_2") (pintype "passive"))
      (node (ref "R9") (pin "2") (pinfunction "2_2") (pintype "passive"))
      (node (ref "R9") (pin "4") (pinfunction "4_4") (pintype "passive"))
    )
    (net (code "78") (name "Net-(D13-Pad2)") (class "Default")
      (node (ref "D13") (pin "2") (pinfunction "2_2") (pintype "passive"))
      (node (ref "R10") (pin "2") (pinfunction "2_2") (pintype "passive"))
      (node (ref "R10") (pin "4") (pinfunction "4_4") (pintype "passive"))
    )
    (net (code "79") (name "Net-(D14-Pad2)") (class "Default")
      (node (ref "D14") (pin "2") (pinfunction "2_2") (pintype "passive"))
      (node (ref "R8") (pin "2") (pinfunction "2_2") (pintype "passive"))
      (node (ref "R8") (pin "4") (pinfunction "4_4") (pintype "passive"))
    )
    (net (code "80") (name "Net-(K1-Pad1)") (class "Default")
      (node (ref "K1") (pin "1") (pinfunction "1_1") (pintype "passive"))
      (node (ref "K1") (pin "4") (pinfunction "4_4") (pintype "passive"))
      (node (ref "K5") (pin "1") (pinfunction "1_1") (pintype "passive"))
      (node (ref "K5") (pin "4") (pinfunction "4_4") (pintype "passive"))
      (node (ref "R4") (pin "1") (pinfunction "1_1") (pintype "passive"))
      (node (ref "R4") (pin "3") (pinfunction "3_3") (pintype "passive"))
    )
    (net (code "81") (name "Net-(K2-Pad1)") (class "Default")
      (node (ref "K2") (pin "1") (pinfunction "1_1") (pintype "passive"))
      (node (ref "K2") (pin "4") (pinfunction "4_4") (pintype "passive"))
      (node (ref "K6") (pin "1") (pinfunction "1_1") (pintype "passive"))
      (node (ref "K6") (pin "4") (pinfunction "4_4") (pintype "passive"))
      (node (ref "R5") (pin "1") (pinfunction "1_1") (pintype "passive"))
      (node (ref "R5") (pin "3") (pinfunction "3_3") (pintype "passive"))
    )
    (net (code "82") (name "Net-(K3-Pad1)") (class "Default")
      (node (ref "K3") (pin "1") (pinfunction "1_1") (pintype "passive"))
      (node (ref "K3") (pin "4") (pinfunction "4_4") (pintype "passive"))
      (node (ref "K7") (pin "1") (pinfunction "1_1") (pintype "passive"))
      (node (ref "K7") (pin "4") (pinfunction "4_4") (pintype "passive"))
      (node (ref "R6") (pin "1") (pinfunction "1_1") (pintype "passive"))
      (node (ref "R6") (pin "3") (pinfunction "3_3") (pintype "passive"))
    )
    (net (code "83") (name "Net-(K4-Pad1)") (class "Default")
      (node (ref "K4") (pin "1") (pinfunction "1_1") (pintype "passive"))
      (node (ref "K4") (pin "4") (pinfunction "4_4") (pintype "passive"))
      (node (ref "K8") (pin "1") (pinfunction "1_1") (pintype "passive"))
      (node (ref "K8") (pin "4") (pinfunction "4_4") (pintype "passive"))
      (node (ref "R7") (pin "1") (pinfunction "1_1") (pintype "passive"))
      (node (ref "R7") (pin "3") (pinfunction "3_3") (pintype "passive"))
    )
    (net (code "84") (name "Net-(Q5-B)") (class "Default")
      (node (ref "D13") (pin "1") (pinfunction "1_1") (pintype "passive"))
      (node (ref "Q5") (pin "2") (pinfunction "B_2") (pintype "passive"))
    )
    (net (code "85") (name "Net-(Q5-C)") (class "Default")
      (node (ref "D4") (pin "1") (pinfunction "1_1") (pintype "passive"))
      (node (ref "D4") (pin "3") (pinfunction "3_3") (pintype "passive"))
      (node (ref "Q5") (pin "3") (pinfunction "C_3") (pintype "passive"))
      (node (ref "Sp1") (pin "2") (pinfunction "2_2") (pintype "passive"))
      (node (ref "Sp1") (pin "3") (pinfunction "3_3") (pintype "passive"))
    )
    (net (code "86") (name "Net-(S1----)") (class "Default")
      (node (ref "D5") (pin "2") (pinfunction "2_2") (pintype "passive"))
      (node (ref "D5") (pin "4") (pinfunction "4_4") (pintype "passive"))
      (node (ref "S1") (pin "3") (pinfunction "com_3") (pintype "passive"))
      (node (ref "S1") (pin "8") (pinfunction "---_8") (pintype "passive"))
    )
    (net (code "87") (name "Net-(S2----)") (class "Default")
      (node (ref "D6") (pin "2") (pinfunction "2_2") (pintype "passive"))
      (node (ref "D6") (pin "4") (pinfunction "4_4") (pintype "passive"))
      (node (ref "S2") (pin "3") (pinfunction "com_3") (pintype "passive"))
      (node (ref "S2") (pin "8") (pinfunction "---_8") (pintype "passive"))
    )
    (net (code "88") (name "Net-(S3----)") (class "Default")
      (node (ref "D7") (pin "2") (pinfunction "2_2") (pintype "passive"))
      (node (ref "D7") (pin "4") (pinfunction "4_4") (pintype "passive"))
      (node (ref "S3") (pin "3") (pinfunction "com_3") (pintype "passive"))
      (node (ref "S3") (pin "8") (pinfunction "---_8") (pintype "passive"))
    )
    (net (code "89") (name "Net-(S4----)") (class "Default")
      (node (ref "D8") (pin "2") (pinfunction "2_2") (pintype "passive"))
      (node (ref "D8") (pin "4") (pinfunction "4_4") (pintype "passive"))
      (node (ref "S4") (pin "3") (pinfunction "com_3") (pintype "passive"))
      (node (ref "S4") (pin "8") (pinfunction "---_8") (pintype "passive"))
    )
    (net (code "90") (name "Net-(U1-P4.1)") (class "Default")
      (node (ref "U1") (pin "29") (pinfunction "P4.1_29") (pintype "passive"))
      (node (ref "U1-2") (pin "12") (pinfunction "12_12") (pintype "passive"))
    )
    (net (code "91") (name "Net-(U3-XI)") (class "Default")
      (node (ref "C2") (pin "1") (pintype "passive"))
      (node (ref "CYC1") (pin "2") (pinfunction "2_2") (pintype "passive"))
      (node (ref "U3") (pin "7") (pinfunction "XI_7") (pintype "passive"))
    )
    (net (code "92") (name "Net-(U3-XO)") (class "Default")
      (node (ref "C3") (pin "1") (pintype "passive"))
      (node (ref "CYC1") (pin "1") (pinfunction "1_1") (pintype "passive"))
      (node (ref "U3") (pin "8") (pinfunction "XO_8") (pintype "passive"))
    )
    (net (code "93") (name "V2.5") (class "Default")
      (node (ref "U1") (pin "11") (pinfunction "P1.2_11") (pintype "passive"))
      (node (ref "U1-1") (pin "11") (pinfunction "11_11") (pintype "passive"))
    )
    (net (code "94") (name "V33") (class "Default")
      (node (ref "C13") (pin "1") (pinfunction "1_1") (pintype "passive"))
      (node (ref "C14") (pin "2") (pinfunction "2_2") (pintype "passive"))
      (node (ref "J5") (pin "2") (pinfunction "2_2") (pintype "passive"))
      (node (ref "U3") (pin "4") (pinfunction "V3_4") (pintype "passive"))
    )
    (net (code "95") (name "VCC") (class "Default")
      (node (ref "C10") (pin "2") (pinfunction "2_2") (pintype "passive"))
      (node (ref "C4") (pin "1") (pinfunction "1_1") (pintype "passive"))
      (node (ref "C5") (pin "1") (pinfunction "1_1") (pintype "passive"))
      (node (ref "C6") (pin "1") (pinfunction "1_1") (pintype "passive"))
      (node (ref "C7") (pin "1") (pinfunction "1_1") (pintype "passive"))
      (node (ref "C8") (pin "2") (pinfunction "2_2") (pintype "passive"))
      (node (ref "D1") (pin "1") (pinfunction "1_1") (pintype "passive"))
      (node (ref "D14") (pin "1") (pinfunction "1_1") (pintype "passive"))
      (node (ref "D2") (pin "1") (pinfunction "1_1") (pintype "passive"))
      (node (ref "Kp") (pin "2") (pinfunction "2_2") (pintype "passive"))
      (node (ref "Q5") (pin "1") (pinfunction "E_1") (pintype "passive"))
      (node (ref "U1") (pin "18") (pinfunction "VCC_18") (pintype "passive"))
      (node (ref "U1-1") (pin "18") (pinfunction "18_18") (pintype "passive"))
      (node (ref "U2") (pin "2") (pinfunction "VCC_2") (pintype "passive"))
      (node (ref "U6") (pin "28") (pinfunction "VCC_28") (pintype "passive"))
      (node (ref "U6-2") (pin "14") (pinfunction "14_14") (pintype "passive"))
      (node (ref "U7") (pin "20") (pinfunction "VCC_20") (pintype "power_in"))
    )
    (net (code "96") (name "VCCU") (class "Default")
      (node (ref "C1") (pin "2") (pinfunction "2_2") (pintype "passive"))
      (node (ref "C11") (pin "1") (pinfunction "1_1") (pintype "passive"))
      (node (ref "D11") (pin "1") (pinfunction "1_1") (pintype "passive"))
      (node (ref "J3") (pin "1") (pinfunction "1_1") (pintype "passive"))
      (node (ref "J4") (pin "1") (pinfunction "1_1") (pintype "passive"))
      (node (ref "J5") (pin "1") (pinfunction "1_1") (pintype "passive"))
      (node (ref "Kp") (pin "1") (pinfunction "1_1") (pintype "passive"))
      (node (ref "U3") (pin "16") (pinfunction "VCC_16") (pintype "passive"))
    )
    (net (code "97") (name "unconnected-(Kp-Pad3)") (class "Default")
      (node (ref "Kp") (pin "3") (pinfunction "3_3") (pintype "passive"))
    )
    (net (code "98") (name "unconnected-(Kp-Pad4)") (class "Default")
      (node (ref "Kp") (pin "4") (pinfunction "4_4") (pintype "passive"))
    )
    (net (code "99") (name "unconnected-(Kp-Pad5)") (class "Default")
      (node (ref "Kp") (pin "5") (pinfunction "5_5") (pintype "passive"))
    )
    (net (code "100") (name "unconnected-(Kp-Pad6)") (class "Default")
      (node (ref "Kp") (pin "6") (pinfunction "6_6") (pintype "passive"))
    )
    (net (code "101") (name "unconnected-(U2-N.C.-Pad17)") (class "Default")
      (node (ref "U2") (pin "17") (pinfunction "N.C._17") (pintype "passive"))
    )
    (net (code "102") (name "unconnected-(U3-CTS#-Pad9)") (class "Default")
      (node (ref "U3") (pin "9") (pinfunction "CTS#_9") (pintype "passive"))
    )
    (net (code "103") (name "unconnected-(U3-DCD#-Pad12)") (class "Default")
      (node (ref "U3") (pin "12") (pinfunction "DCD#_12") (pintype "passive"))
    )
    (net (code "104") (name "unconnected-(U3-DSR#-Pad10)") (class "Default")
      (node (ref "U3") (pin "10") (pinfunction "DSR#_10") (pintype "passive"))
    )
    (net (code "105") (name "unconnected-(U3-DTR#-Pad13)") (class "Default")
      (node (ref "U3") (pin "13") (pinfunction "DTR#_13") (pintype "passive"))
    )
    (net (code "106") (name "unconnected-(U3-R232-Pad15)") (class "Default")
      (node (ref "U3") (pin "15") (pinfunction "R232_15") (pintype "passive"))
    )
    (net (code "107") (name "unconnected-(U3-RI#-Pad11)") (class "Default")
      (node (ref "U3") (pin "11") (pinfunction "RI#_11") (pintype "passive"))
    )
    (net (code "108") (name "unconnected-(U3-RTS#-Pad14)") (class "Default")
      (node (ref "U3") (pin "14") (pinfunction "RTS#_14") (pintype "passive"))
    )
  )
)
